# power_ver2.net
KiCad netlist of a schematic drawn in EAGLE
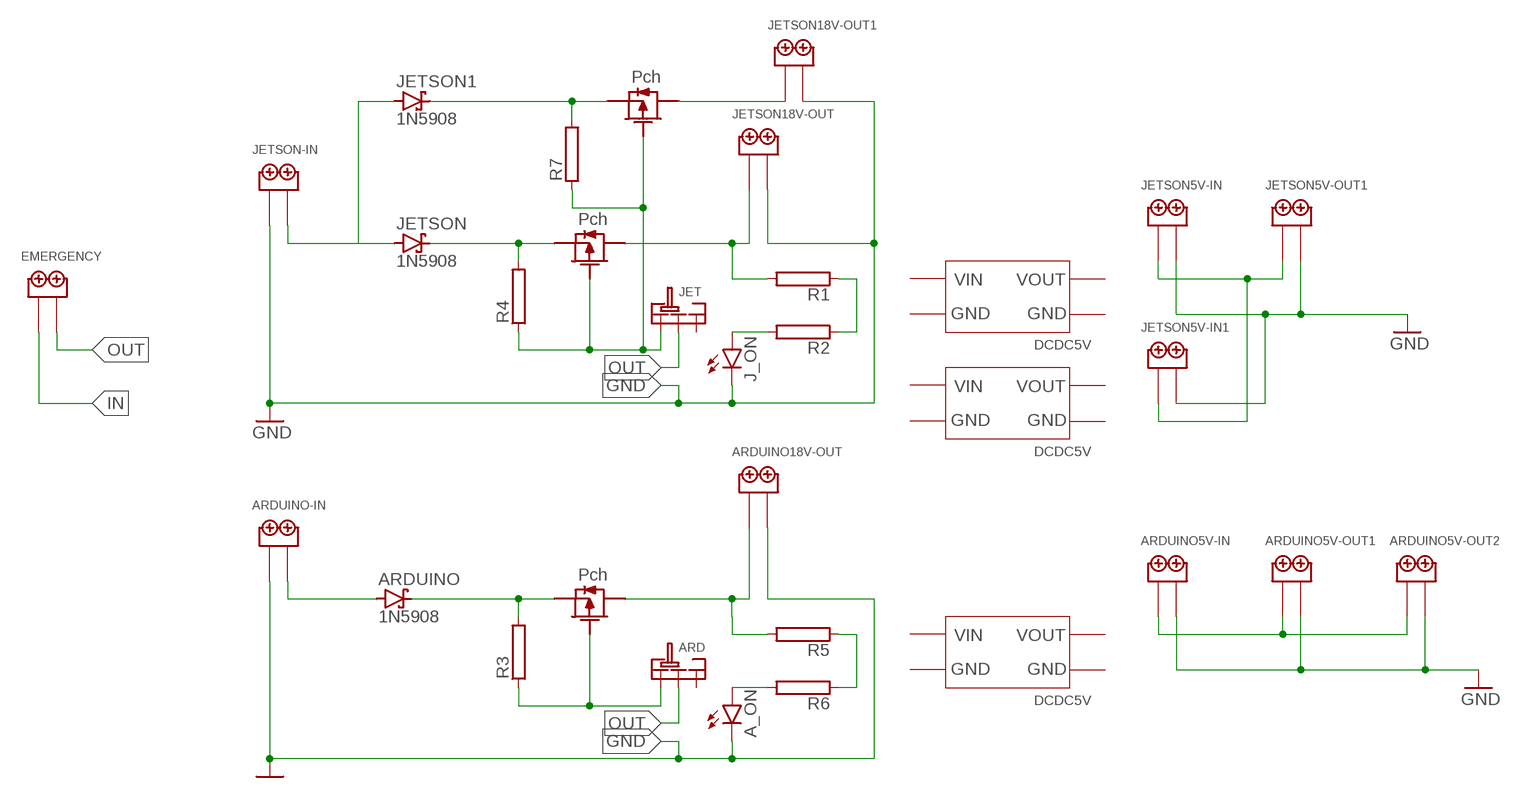
[diagram p0: schematic, sheet 1]

(export (version "E")
  (design (tool "Eeschema 10.0.6"))
  (components
    (comp (ref "ARD")
      (value "SRIDE_SWITCH")
      (footprint "eagle-import:SRIDE_SWITCH")
      (libsource (lib "eagle-import") (part "SRIDE_SWITCH"))
    )
    (comp (ref "ARDUINO")
      (value "1N5908")
      (footprint "eagle-import:C4111-15")
      (libsource (lib "eagle-import") (part "1N5908"))
    )
    (comp (ref "ARDUINO-IN")
      (value "2PIN")
      (footprint "eagle-import:2PIN")
      (libsource (lib "eagle-import") (part "2PIN"))
    )
    (comp (ref "ARDUINO5V-IN")
      (value "2PIN")
      (footprint "eagle-import:2PIN")
      (libsource (lib "eagle-import") (part "2PIN"))
    )
    (comp (ref "ARDUINO5V-OUT1")
      (value "2PIN")
      (footprint "eagle-import:2PIN")
      (libsource (lib "eagle-import") (part "2PIN"))
    )
    (comp (ref "ARDUINO5V-OUT2")
      (value "2PIN")
      (footprint "eagle-import:2PIN")
      (libsource (lib "eagle-import") (part "2PIN"))
    )
    (comp (ref "ARDUINO18V-OUT")
      (value "2PIN")
      (footprint "eagle-import:2PIN")
      (libsource (lib "eagle-import") (part "2PIN"))
    )
    (comp (ref "A_ON")
      (value "LED5MM")
      (footprint "eagle-import:LED5MM")
      (libsource (lib "eagle-import") (part "LED5MM"))
    )
    (comp (ref "EMERGENCY")
      (value "2PIN")
      (footprint "eagle-import:2PIN")
      (libsource (lib "eagle-import") (part "2PIN"))
    )
    (comp (ref "JET")
      (value "SRIDE_SWITCH")
      (footprint "eagle-import:SRIDE_SWITCH")
      (libsource (lib "eagle-import") (part "SRIDE_SWITCH"))
    )
    (comp (ref "JETSON")
      (value "1N5908")
      (footprint "eagle-import:C4111-15")
      (libsource (lib "eagle-import") (part "1N5908"))
    )
    (comp (ref "JETSON-IN")
      (value "2PIN")
      (footprint "eagle-import:2PIN")
      (libsource (lib "eagle-import") (part "2PIN"))
    )
    (comp (ref "JETSON1")
      (value "1N5908")
      (footprint "eagle-import:C4111-15")
      (libsource (lib "eagle-import") (part "1N5908"))
    )
    (comp (ref "JETSON5V-IN")
      (value "2PIN")
      (footprint "eagle-import:2PIN")
      (libsource (lib "eagle-import") (part "2PIN"))
    )
    (comp (ref "JETSON5V-IN1")
      (value "2PIN")
      (footprint "eagle-import:2PIN")
      (libsource (lib "eagle-import") (part "2PIN"))
    )
    (comp (ref "JETSON5V-OUT1")
      (value "2PIN")
      (footprint "eagle-import:2PIN")
      (libsource (lib "eagle-import") (part "2PIN"))
    )
    (comp (ref "JETSON18V-OUT")
      (value "2PIN")
      (footprint "eagle-import:2PIN")
      (libsource (lib "eagle-import") (part "2PIN"))
    )
    (comp (ref "JETSON18V-OUT1")
      (value "2PIN")
      (footprint "eagle-import:2PIN")
      (libsource (lib "eagle-import") (part "2PIN"))
    )
    (comp (ref "J_ON")
      (value "LED5MM")
      (footprint "eagle-import:LED5MM")
      (libsource (lib "eagle-import") (part "LED5MM"))
    )
    (comp (ref "R1")
      (value "RAC01")
      (footprint "eagle-import:AC01")
      (libsource (lib "eagle-import") (part "RAC01"))
    )
    (comp (ref "R2")
      (value "RAC01")
      (footprint "eagle-import:AC01")
      (libsource (lib "eagle-import") (part "RAC01"))
    )
    (comp (ref "R3")
      (value "RAC01")
      (footprint "eagle-import:AC01")
      (libsource (lib "eagle-import") (part "RAC01"))
    )
    (comp (ref "R4")
      (value "RAC01")
      (footprint "eagle-import:AC01")
      (libsource (lib "eagle-import") (part "RAC01"))
    )
    (comp (ref "R5")
      (value "RAC01")
      (footprint "eagle-import:AC01")
      (libsource (lib "eagle-import") (part "RAC01"))
    )
    (comp (ref "R6")
      (value "RAC01")
      (footprint "eagle-import:AC01")
      (libsource (lib "eagle-import") (part "RAC01"))
    )
    (comp (ref "R7")
      (value "RAC01")
      (footprint "eagle-import:AC01")
      (libsource (lib "eagle-import") (part "RAC01"))
    )
    (comp (ref "U$1")
      (value "2SJ334")
      (footprint "eagle-import:2SJ334")
      (libsource (lib "eagle-import") (part "2SJ334"))
    )
    (comp (ref "U$2")
      (value "DCDCDEV")
      (footprint "eagle-import:DCDCDEV")
      (libsource (lib "eagle-import") (part "DCDCDEV"))
    )
    (comp (ref "U$4")
      (value "2SJ334")
      (footprint "eagle-import:2SJ334")
      (libsource (lib "eagle-import") (part "2SJ334"))
    )
    (comp (ref "U$5")
      (value "2SJ334")
      (footprint "eagle-import:2SJ334")
      (libsource (lib "eagle-import") (part "2SJ334"))
    )
    (comp (ref "U$6")
      (value "DCDCDEV")
      (footprint "eagle-import:DCDCDEV")
      (libsource (lib "eagle-import") (part "DCDCDEV"))
    )
    (comp (ref "U$23")
      (value "DCDCDEV")
      (footprint "eagle-import:DCDCDEV")
      (libsource (lib "eagle-import") (part "DCDCDEV"))
    )
  )
  (nets
    (net (code "1") (name "GND") (class "Default")
      (node (ref "ARDUINO-IN") (pin "P$1") (pinfunction "P$1_P$1") (pintype "bidirectional"))
      (node (ref "ARDUINO18V-OUT") (pin "P$2") (pinfunction "P$2_P$2") (pintype "bidirectional"))
      (node (ref "ARDUINO5V-IN") (pin "P$2") (pinfunction "P$2_P$2") (pintype "bidirectional"))
      (node (ref "ARDUINO5V-OUT1") (pin "P$2") (pinfunction "P$2_P$2") (pintype "bidirectional"))
      (node (ref "ARDUINO5V-OUT2") (pin "P$2") (pinfunction "P$2_P$2") (pintype "bidirectional"))
      (node (ref "A_ON") (pin "K") (pinfunction "C_K") (pintype "passive"))
      (node (ref "JETSON-IN") (pin "P$1") (pinfunction "P$1_P$1") (pintype "bidirectional"))
      (node (ref "JETSON18V-OUT") (pin "P$2") (pinfunction "P$2_P$2") (pintype "bidirectional"))
      (node (ref "JETSON18V-OUT1") (pin "P$2") (pinfunction "P$2_P$2") (pintype "bidirectional"))
      (node (ref "JETSON5V-IN") (pin "P$2") (pinfunction "P$2_P$2") (pintype "bidirectional"))
      (node (ref "JETSON5V-IN1") (pin "P$2") (pinfunction "P$2_P$2") (pintype "bidirectional"))
      (node (ref "JETSON5V-OUT1") (pin "P$2") (pinfunction "P$2_P$2") (pintype "bidirectional"))
      (node (ref "J_ON") (pin "K") (pinfunction "C_K") (pintype "passive"))
    )
    (net (code "2") (name "IN") (class "Default")
      (node (ref "EMERGENCY") (pin "P$1") (pinfunction "P$1_P$1") (pintype "bidirectional"))
    )
    (net (code "3") (name "Net-(ARD-PadL)") (class "Default")
      (node (ref "ARD") (pin "L") (pinfunction "L_L") (pintype "bidirectional"))
      (node (ref "R3") (pin "1") (pinfunction "1_1") (pintype "passive"))
      (node (ref "U$5") (pin "GATE") (pinfunction "GATE_GATE") (pintype "bidirectional"))
    )
    (net (code "4") (name "Net-(ARDUINO-IN-PadP$2)") (class "Default")
      (node (ref "ARDUINO") (pin "A") (pinfunction "A_A") (pintype "passive"))
      (node (ref "ARDUINO-IN") (pin "P$2") (pinfunction "P$2_P$2") (pintype "bidirectional"))
    )
    (net (code "5") (name "Net-(ARDUINO-PadC)") (class "Default")
      (node (ref "ARDUINO") (pin "C") (pinfunction "C_C") (pintype "passive"))
      (node (ref "R3") (pin "2") (pinfunction "2_2") (pintype "passive"))
      (node (ref "U$5") (pin "SOURCE") (pinfunction "SOURCE_SOURCE") (pintype "bidirectional"))
    )
    (net (code "6") (name "Net-(ARDUINO5V-IN-PadP$1)") (class "Default")
      (node (ref "ARDUINO5V-IN") (pin "P$1") (pinfunction "P$1_P$1") (pintype "bidirectional"))
      (node (ref "ARDUINO5V-OUT1") (pin "P$1") (pinfunction "P$1_P$1") (pintype "bidirectional"))
      (node (ref "ARDUINO5V-OUT2") (pin "P$1") (pinfunction "P$1_P$1") (pintype "bidirectional"))
    )
    (net (code "7") (name "Net-(ARDUINO18V-OUT-PadP$1)") (class "Default")
      (node (ref "ARDUINO18V-OUT") (pin "P$1") (pinfunction "P$1_P$1") (pintype "bidirectional"))
      (node (ref "R5") (pin "2") (pinfunction "2_2") (pintype "passive"))
      (node (ref "U$5") (pin "DRAIN") (pinfunction "DRAIN_DRAIN") (pintype "bidirectional"))
    )
    (net (code "8") (name "Net-(A_ON-PadA)") (class "Default")
      (node (ref "A_ON") (pin "A") (pinfunction "A_A") (pintype "passive"))
      (node (ref "R6") (pin "2") (pinfunction "2_2") (pintype "passive"))
    )
    (net (code "9") (name "Net-(JET-PadL)") (class "Default")
      (node (ref "JET") (pin "L") (pinfunction "L_L") (pintype "bidirectional"))
      (node (ref "R4") (pin "1") (pinfunction "1_1") (pintype "passive"))
      (node (ref "R7") (pin "1") (pinfunction "1_1") (pintype "passive"))
      (node (ref "U$1") (pin "GATE") (pinfunction "GATE_GATE") (pintype "bidirectional"))
      (node (ref "U$4") (pin "GATE") (pinfunction "GATE_GATE") (pintype "bidirectional"))
    )
    (net (code "10") (name "Net-(JETSON-IN-PadP$2)") (class "Default")
      (node (ref "JETSON") (pin "A") (pinfunction "A_A") (pintype "passive"))
      (node (ref "JETSON-IN") (pin "P$2") (pinfunction "P$2_P$2") (pintype "bidirectional"))
      (node (ref "JETSON1") (pin "A") (pinfunction "A_A") (pintype "passive"))
    )
    (net (code "11") (name "Net-(JETSON-PadC)") (class "Default")
      (node (ref "JETSON") (pin "C") (pinfunction "C_C") (pintype "passive"))
      (node (ref "R4") (pin "2") (pinfunction "2_2") (pintype "passive"))
      (node (ref "U$4") (pin "SOURCE") (pinfunction "SOURCE_SOURCE") (pintype "bidirectional"))
    )
    (net (code "12") (name "Net-(JETSON1-PadC)") (class "Default")
      (node (ref "JETSON1") (pin "C") (pinfunction "C_C") (pintype "passive"))
      (node (ref "R7") (pin "2") (pinfunction "2_2") (pintype "passive"))
      (node (ref "U$1") (pin "SOURCE") (pinfunction "SOURCE_SOURCE") (pintype "bidirectional"))
    )
    (net (code "13") (name "Net-(JETSON5V-IN-PadP$1)") (class "Default")
      (node (ref "JETSON5V-IN") (pin "P$1") (pinfunction "P$1_P$1") (pintype "bidirectional"))
      (node (ref "JETSON5V-IN1") (pin "P$1") (pinfunction "P$1_P$1") (pintype "bidirectional"))
      (node (ref "JETSON5V-OUT1") (pin "P$1") (pinfunction "P$1_P$1") (pintype "bidirectional"))
    )
    (net (code "14") (name "Net-(JETSON18V-OUT-PadP$1)") (class "Default")
      (node (ref "JETSON18V-OUT") (pin "P$1") (pinfunction "P$1_P$1") (pintype "bidirectional"))
      (node (ref "R1") (pin "2") (pinfunction "2_2") (pintype "passive"))
      (node (ref "U$4") (pin "DRAIN") (pinfunction "DRAIN_DRAIN") (pintype "bidirectional"))
    )
    (net (code "15") (name "Net-(JETSON18V-OUT1-PadP$1)") (class "Default")
      (node (ref "JETSON18V-OUT1") (pin "P$1") (pinfunction "P$1_P$1") (pintype "bidirectional"))
      (node (ref "U$1") (pin "DRAIN") (pinfunction "DRAIN_DRAIN") (pintype "bidirectional"))
    )
    (net (code "16") (name "Net-(J_ON-PadA)") (class "Default")
      (node (ref "J_ON") (pin "A") (pinfunction "A_A") (pintype "passive"))
      (node (ref "R2") (pin "2") (pinfunction "2_2") (pintype "passive"))
    )
    (net (code "17") (name "Net-(R1-Pad1)") (class "Default")
      (node (ref "R1") (pin "1") (pinfunction "1_1") (pintype "passive"))
      (node (ref "R2") (pin "1") (pinfunction "1_1") (pintype "passive"))
    )
    (net (code "18") (name "Net-(R5-Pad1)") (class "Default")
      (node (ref "R5") (pin "1") (pinfunction "1_1") (pintype "passive"))
      (node (ref "R6") (pin "1") (pinfunction "1_1") (pintype "passive"))
    )
    (net (code "19") (name "OUT") (class "Default")
      (node (ref "ARD") (pin "LR") (pinfunction "LR_LR") (pintype "bidirectional"))
      (node (ref "EMERGENCY") (pin "P$2") (pinfunction "P$2_P$2") (pintype "bidirectional"))
      (node (ref "JET") (pin "LR") (pinfunction "LR_LR") (pintype "bidirectional"))
    )
    (net (code "20") (name "unconnected-(ARD-PadR)") (class "Default")
      (node (ref "ARD") (pin "R") (pinfunction "R_R") (pintype "bidirectional"))
    )
    (net (code "21") (name "unconnected-(JET-PadR)") (class "Default")
      (node (ref "JET") (pin "R") (pinfunction "R_R") (pintype "bidirectional"))
    )
  )
)
